# USB_HS.net
KiCad netlist of a schematic drawn in Altium Designer
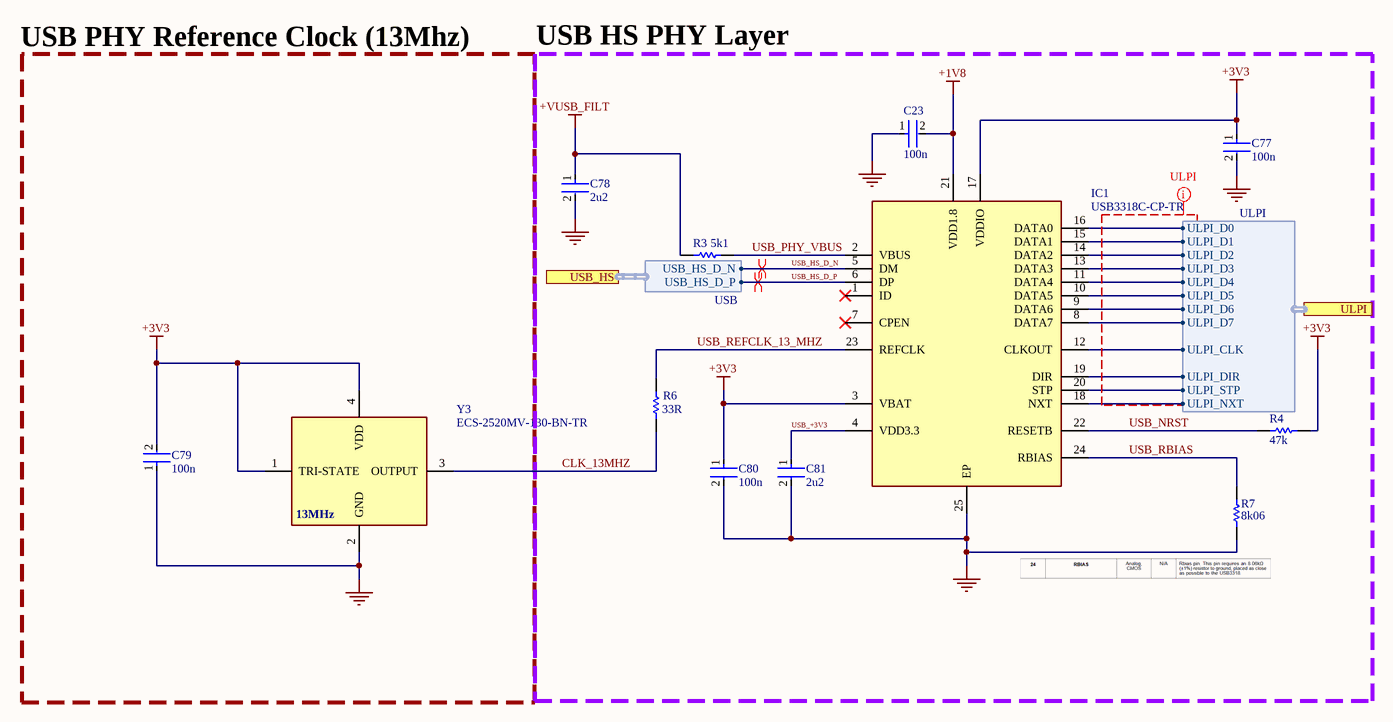
[diagram p0: USB_HS.SchDoc]

(export (version "E")
  (design (tool "Eeschema 10.0.6"))
  (components
    (comp (ref "C23")
      (value "GCM155R71H104ME02J")
      (footprint "FP-GCM155-0_05-IPC_A")
      (description "Ceramic Capacitor for Automotive 100nF ±20% 50VDC X7R 0402 Paper T/R")
      (fields (field (name "CAPACITANCE") "100n"))
      (libsource (lib "Altium Content Vault") (part "02cd4be3c70576c341d710602a673aa"))
    )
    (comp (ref "C77")
      (value "GCM155R71H104ME02J")
      (footprint "FP-GCM155-0_05-IPC_A")
      (description "Ceramic Capacitor for Automotive 100nF ±20% 50VDC X7R 0402 Paper T/R")
      (fields (field (name "CAPACITANCE") "100n"))
      (libsource (lib "Altium Content Vault") (part "02cd4be3c70576c341d710602a673aa"))
    )
    (comp (ref "C78")
      (value "GCM188C71A225KE02D")
      (footprint "FP-GCH188-0_1-e0_2_0_5-MFG")
      (description "GCM188C71A225KE02D Multilayer Ceramic Capacitor, 2.2 uF, 10 V, ± 10%, X7S, 0603 [1608 Metric]")
      (fields (field (name "CAPACITANCE") "2u2"))
      (libsource (lib "Altium Content Vault") (part "b4654b650e69147ec39a6b967a45e02"))
    )
    (comp (ref "C79")
      (value "GCM155R71H104ME02J")
      (footprint "FP-GCM155-0_05-IPC_A")
      (description "Ceramic Capacitor for Automotive 100nF ±20% 50VDC X7R 0402 Paper T/R")
      (fields (field (name "CAPACITANCE") "100n"))
      (libsource (lib "Altium Content Vault") (part "02cd4be3c70576c341d710602a673aa"))
    )
    (comp (ref "C80")
      (value "GCM155R71H104ME02J")
      (footprint "FP-GCM155-0_05-IPC_A")
      (description "Ceramic Capacitor for Automotive 100nF ±20% 50VDC X7R 0402 Paper T/R")
      (fields (field (name "CAPACITANCE") "100n"))
      (libsource (lib "Altium Content Vault") (part "02cd4be3c70576c341d710602a673aa"))
    )
    (comp (ref "C81")
      (value "GCM188C71A225KE02D")
      (footprint "FP-GCH188-0_1-e0_2_0_5-MFG")
      (description "GCM188C71A225KE02D Multilayer Ceramic Capacitor, 2.2 uF, 10 V, ± 10%, X7S, 0603 [1608 Metric]")
      (fields (field (name "CAPACITANCE") "2u2"))
      (libsource (lib "Altium Content Vault") (part "b4654b650e69147ec39a6b967a45e02"))
    )
    (comp (ref "IC1")
      (value "USB3318C-CP-TR")
      (footprint "QFN50P400X400X100-25N-D")
      (description "Integrated Circuit")
      (fields (field (name "MOUSER PART NUMBER") "886-USB3318C-CP-TR"))
      (libsource (lib "audio_dev_pcb") (part "USB3318C-CP-TR"))
    )
    (comp (ref "R3")
      (value "RC0402JR-075K1L")
      (footprint "RESC1005X40X25ML05T10")
      (fields (field (name "MANUFACTURER") "Yageo / Phycomp") (field (name "RESISTANCE") "5k1"))
      (libsource (lib "Altium Content Vault") (part "RES"))
    )
    (comp (ref "R4")
      (value "RC0402JR-0747KL")
      (footprint "RESC1005X40X25LL05T10")
      (fields (field (name "MANUFACTURER") "Yageo / Phycomp") (field (name "RESISTANCE") "47k"))
      (libsource (lib "Altium Content Vault") (part "RES"))
    )
    (comp (ref "R6")
      (value "RC0402JR-1333RL")
      (footprint "RESC1005X40X25ML05T10")
      (fields (field (name "MANUFACTURER") "Yageo") (field (name "RESISTANCE") "33R"))
      (libsource (lib "Altium Content Vault") (part "RES"))
    )
    (comp (ref "R7")
      (value "RC0402FR-07806KL")
      (footprint "RESC1005X40X25NL05T10")
      (fields (field (name "MANUFACTURER") "Yageo / Phycomp") (field (name "RESISTANCE") "8k06"))
      (libsource (lib "Altium Content Vault") (part "RES"))
    )
    (comp (ref "Y3")
      (value "ECS-2520MV-130-BN-TR")
      (footprint "ECS2520MV130BNTR")
      (description "Crystal or Oscillator")
      (fields (field (name "MOUSER PART NUMBER") "520-S2520MV130BNTR"))
      (libsource (lib "audio_dev_pcb") (part "ECS-2520MV-130-BN-TR"))
    )
  )
  (nets
    (net (code "3") (name "+1V8") (class "Default")
      (node (ref "C23") (pin "2") (pinfunction "2_2") (pintype "passive"))
      (node (ref "IC1") (pin "21") (pinfunction "VDD1.8_21") (pintype "passive"))
    )
    (net (code "4") (name "+3V3") (class "Default")
      (node (ref "C77") (pin "1") (pinfunction "1_1") (pintype "passive"))
      (node (ref "C79") (pin "2") (pinfunction "2_2") (pintype "passive"))
      (node (ref "C80") (pin "1") (pinfunction "1_1") (pintype "passive"))
      (node (ref "IC1") (pin "17") (pinfunction "VDDIO_17") (pintype "passive"))
      (node (ref "IC1") (pin "3") (pinfunction "VBAT_3") (pintype "passive"))
      (node (ref "R4") (pin "2") (pinfunction "2_2") (pintype "passive"))
      (node (ref "Y3") (pin "1") (pinfunction "TRI-STATE_1") (pintype "passive"))
      (node (ref "Y3") (pin "4") (pinfunction "VDD_4") (pintype "passive"))
    )
    (net (code "5") (name "+VUSB_FILT") (class "Default")
      (node (ref "C78") (pin "1") (pinfunction "1_1") (pintype "passive"))
      (node (ref "R3") (pin "1") (pinfunction "1_1") (pintype "passive"))
    )
    (net (code "6") (name "/CLK_13MHZ") (class "Default")
      (node (ref "R6") (pin "2") (pinfunction "2_2") (pintype "passive"))
      (node (ref "Y3") (pin "3") (pinfunction "OUTPUT_3") (pintype "passive"))
    )
    (net (code "7") (name "/ULPI_CLK") (class "Default")
      (node (ref "IC1") (pin "12") (pinfunction "CLKOUT_12") (pintype "passive"))
    )
    (net (code "8") (name "/ULPI_D0") (class "Default")
      (node (ref "IC1") (pin "16") (pinfunction "DATA0_16") (pintype "passive"))
    )
    (net (code "9") (name "/ULPI_D1") (class "Default")
      (node (ref "IC1") (pin "15") (pinfunction "DATA1_15") (pintype "passive"))
    )
    (net (code "10") (name "/ULPI_D2") (class "Default")
      (node (ref "IC1") (pin "14") (pinfunction "DATA2_14") (pintype "passive"))
    )
    (net (code "11") (name "/ULPI_D3") (class "Default")
      (node (ref "IC1") (pin "13") (pinfunction "DATA3_13") (pintype "passive"))
    )
    (net (code "12") (name "/ULPI_D4") (class "Default")
      (node (ref "IC1") (pin "11") (pinfunction "DATA4_11") (pintype "passive"))
    )
    (net (code "13") (name "/ULPI_D5") (class "Default")
      (node (ref "IC1") (pin "10") (pinfunction "DATA5_10") (pintype "passive"))
    )
    (net (code "14") (name "/ULPI_D6") (class "Default")
      (node (ref "IC1") (pin "9") (pinfunction "DATA6_9") (pintype "passive"))
    )
    (net (code "15") (name "/ULPI_D7") (class "Default")
      (node (ref "IC1") (pin "8") (pinfunction "DATA7_8") (pintype "passive"))
    )
    (net (code "16") (name "/ULPI_DIR") (class "Default")
      (node (ref "IC1") (pin "19") (pinfunction "DIR_19") (pintype "passive"))
    )
    (net (code "17") (name "/ULPI_NXT") (class "Default")
      (node (ref "IC1") (pin "18") (pinfunction "NXT_18") (pintype "passive"))
    )
    (net (code "18") (name "/ULPI_STP") (class "Default")
      (node (ref "IC1") (pin "20") (pinfunction "STP_20") (pintype "passive"))
    )
    (net (code "19") (name "/USB_+3V3") (class "Default")
      (node (ref "C81") (pin "1") (pinfunction "1_1") (pintype "passive"))
      (node (ref "IC1") (pin "4") (pinfunction "VDD3.3_4") (pintype "passive"))
    )
    (net (code "20") (name "/USB_HS_D_N") (class "Default")
      (node (ref "IC1") (pin "5") (pinfunction "DM_5") (pintype "passive"))
    )
    (net (code "21") (name "/USB_HS_D_P") (class "Default")
      (node (ref "IC1") (pin "6") (pinfunction "DP_6") (pintype "passive"))
    )
    (net (code "22") (name "/USB_NRST") (class "Default")
      (node (ref "IC1") (pin "22") (pinfunction "RESETB_22") (pintype "passive"))
      (node (ref "R4") (pin "1") (pinfunction "1_1") (pintype "passive"))
    )
    (net (code "23") (name "/USB_PHY_VBUS") (class "Default")
      (node (ref "IC1") (pin "2") (pinfunction "VBUS_2") (pintype "passive"))
      (node (ref "R3") (pin "2") (pinfunction "2_2") (pintype "passive"))
    )
    (net (code "24") (name "/USB_RBIAS") (class "Default")
      (node (ref "IC1") (pin "24") (pinfunction "RBIAS_24") (pintype "passive"))
      (node (ref "R7") (pin "2") (pinfunction "2_2") (pintype "passive"))
    )
    (net (code "25") (name "/USB_REFCLK_13_MHZ") (class "Default")
      (node (ref "IC1") (pin "23") (pinfunction "REFCLK_23") (pintype "passive"))
      (node (ref "R6") (pin "1") (pinfunction "1_1") (pintype "passive"))
    )
    (net (code "28") (name "GND") (class "Default")
      (node (ref "C23") (pin "1") (pinfunction "1_1") (pintype "passive"))
      (node (ref "C77") (pin "2") (pinfunction "2_2") (pintype "passive"))
      (node (ref "C78") (pin "2") (pinfunction "2_2") (pintype "passive"))
      (node (ref "C79") (pin "1") (pinfunction "1_1") (pintype "passive"))
      (node (ref "C80") (pin "2") (pinfunction "2_2") (pintype "passive"))
      (node (ref "C81") (pin "2") (pinfunction "2_2") (pintype "passive"))
      (node (ref "IC1") (pin "25") (pinfunction "EP_25") (pintype "passive"))
      (node (ref "R7") (pin "1") (pinfunction "1_1") (pintype "passive"))
      (node (ref "Y3") (pin "2") (pinfunction "GND_2") (pintype "passive"))
    )
    (net (code "29") (name "unconnected-(IC1-CPEN-Pad7)") (class "Default")
      (node (ref "IC1") (pin "7") (pinfunction "CPEN_7") (pintype "passive+no_connect"))
    )
    (net (code "30") (name "unconnected-(IC1-ID-Pad1)") (class "Default")
      (node (ref "IC1") (pin "1") (pinfunction "ID_1") (pintype "passive+no_connect"))
    )
  )
)
